# 01_STM32F103RCT6_RNF24L01.net
KiCad netlist of a schematic drawn in Altium Designer
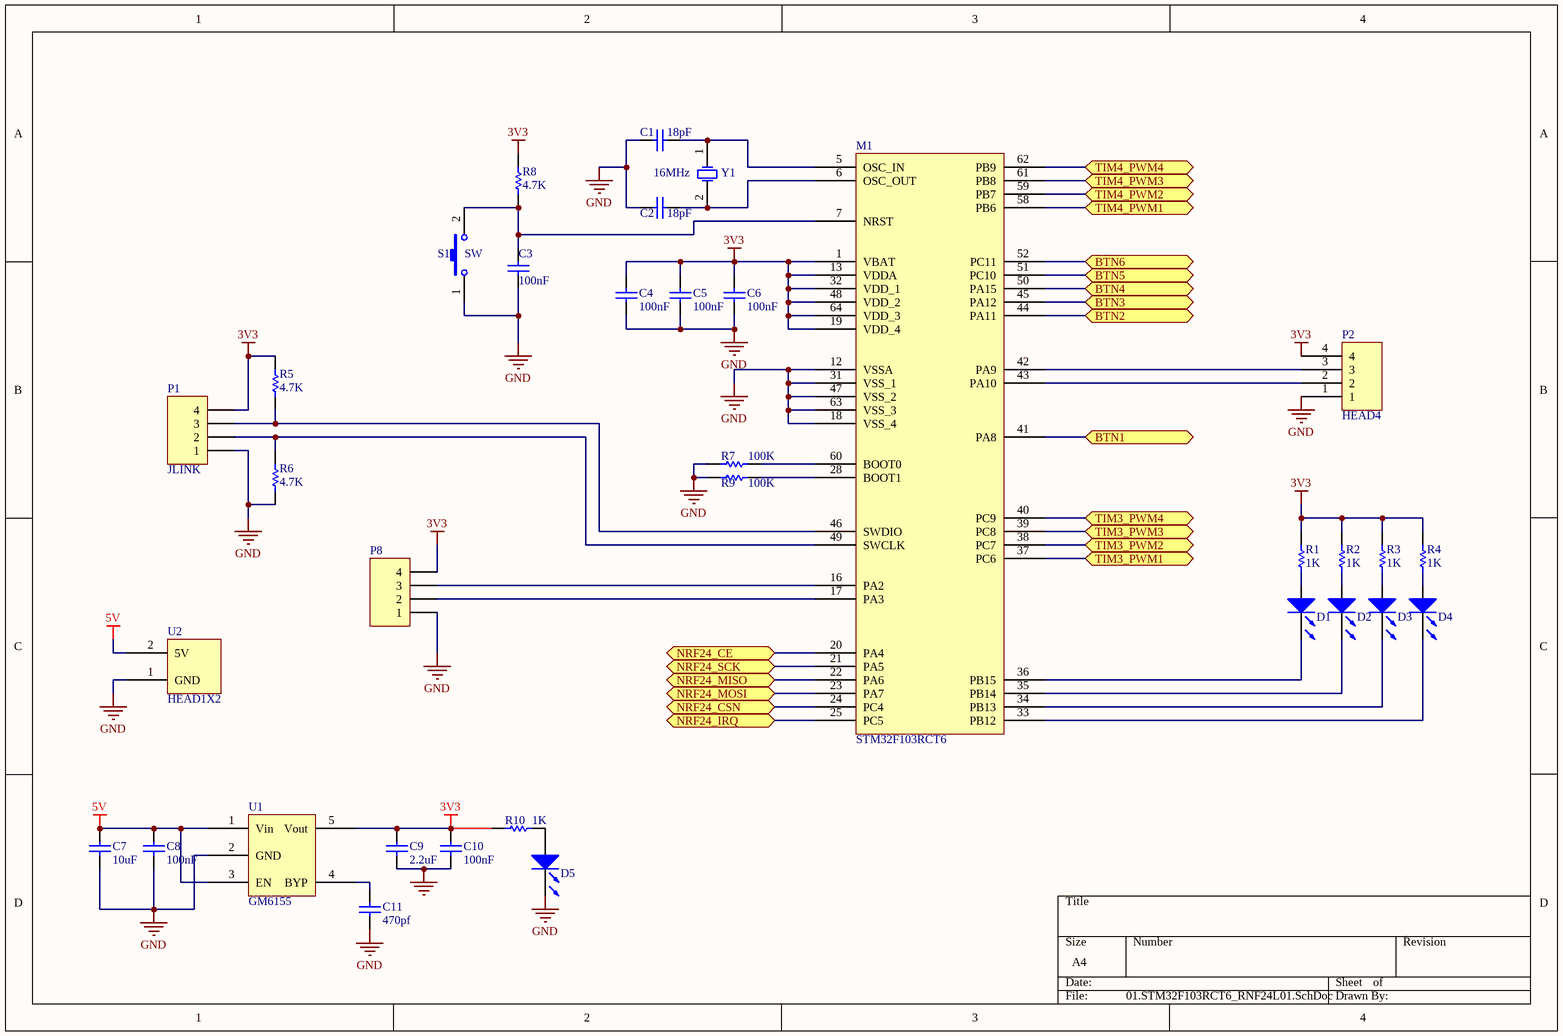
[diagram p0: 01.STM32F103RCT6_RNF24L01.SchDoc]

(export (version "E")
  (design (tool "Eeschema 10.0.6"))
  (components
    (comp (ref "C1")
      (value "18pF")
      (footprint "C1206")
      (description "Capacitor (Semiconductor SIM Model)")
      (fields (field (name "Comment") "Cap Semi") (field (name "PUBLISHER") "Altium Limited"))
      (libsource (lib "Miscellaneous Devices") (part "Cap Semi"))
    )
    (comp (ref "C2")
      (value "18pF")
      (footprint "C1206")
      (description "Capacitor (Semiconductor SIM Model)")
      (fields (field (name "Comment") "Cap Semi") (field (name "PUBLISHER") "Altium Limited"))
      (libsource (lib "Miscellaneous Devices") (part "Cap Semi"))
    )
    (comp (ref "C3")
      (value "100nF")
      (footprint "0805C")
      (description "Capacitor")
      (fields (field (name "PUBLISHER") "Altium Limited"))
      (libsource (lib "YG_SCH_LIB") (part "Cap"))
    )
    (comp (ref "C4")
      (value "100nF")
      (footprint "0805C")
      (description "Capacitor")
      (fields (field (name "PUBLISHER") "Altium Limited"))
      (libsource (lib "YG_SCH_LIB") (part "Cap"))
    )
    (comp (ref "C5")
      (value "100nF")
      (footprint "0805C")
      (description "Capacitor")
      (fields (field (name "PUBLISHER") "Altium Limited"))
      (libsource (lib "YG_SCH_LIB") (part "Cap"))
    )
    (comp (ref "C6")
      (value "100nF")
      (footprint "0805C")
      (description "Capacitor")
      (fields (field (name "PUBLISHER") "Altium Limited"))
      (libsource (lib "YG_SCH_LIB") (part "Cap"))
    )
    (comp (ref "C7")
      (value "10uF")
      (footprint "0805C")
      (description "Capacitor")
      (fields (field (name "PUBLISHER") "Altium Limited"))
      (libsource (lib "YG_SCH_LIB") (part "Cap"))
    )
    (comp (ref "C8")
      (value "100nF")
      (footprint "0805C")
      (description "Capacitor")
      (fields (field (name "PUBLISHER") "Altium Limited"))
      (libsource (lib "YG_SCH_LIB") (part "Cap"))
    )
    (comp (ref "C9")
      (value "2.2uF")
      (footprint "0805C")
      (description "Capacitor")
      (fields (field (name "PUBLISHER") "Altium Limited"))
      (libsource (lib "YG_SCH_LIB") (part "Cap"))
    )
    (comp (ref "C10")
      (value "100nF")
      (footprint "0805C")
      (description "Capacitor")
      (fields (field (name "PUBLISHER") "Altium Limited"))
      (libsource (lib "YG_SCH_LIB") (part "Cap"))
    )
    (comp (ref "C11")
      (value "470pf")
      (footprint "0805C")
      (description "Capacitor")
      (fields (field (name "PUBLISHER") "Altium Limited"))
      (libsource (lib "YG_SCH_LIB") (part "Cap"))
    )
    (comp (ref "D1")
      (value "LED")
      (footprint "0805_LED")
      (description "Typical RED GaAs LED")
      (fields (field (name "PUBLISHER") "Altium Limited"))
      (libsource (lib "YG_SCH_LIB") (part "LED"))
    )
    (comp (ref "D2")
      (value "LED")
      (footprint "0805_LED")
      (description "Typical RED GaAs LED")
      (fields (field (name "PUBLISHER") "Altium Limited"))
      (libsource (lib "YG_SCH_LIB") (part "LED"))
    )
    (comp (ref "D3")
      (value "LED")
      (footprint "0805_LED")
      (description "Typical RED GaAs LED")
      (fields (field (name "PUBLISHER") "Altium Limited"))
      (libsource (lib "YG_SCH_LIB") (part "LED"))
    )
    (comp (ref "D4")
      (value "LED")
      (footprint "0805_LED")
      (description "Typical RED GaAs LED")
      (fields (field (name "PUBLISHER") "Altium Limited"))
      (libsource (lib "YG_SCH_LIB") (part "LED"))
    )
    (comp (ref "D5")
      (value "LED")
      (footprint "0805_LED")
      (description "Typical RED GaAs LED")
      (fields (field (name "PUBLISHER") "Altium Limited"))
      (libsource (lib "YG_SCH_LIB") (part "LED"))
    )
    (comp (ref "M1")
      (value "STM32F103RCT6")
      (footprint "LQFP64")
      (libsource (lib "020.STM32F103RCT6_RNF24L01") (part "STM32F103RCT6"))
    )
    (comp (ref "P1")
      (value "JLINK")
      (footprint "HDR1X4")
      (description "Header, 4-Pin")
      (fields (field (name "PUBLISHER") "Altium Limited"))
      (libsource (lib "YG_SCH_LIB") (part "Header 4"))
    )
    (comp (ref "P2")
      (value "HEAD4")
      (footprint "HDR1X4")
      (libsource (lib "020.STM32F103RCT6_RNF24L01") (part "HEAD4"))
    )
    (comp (ref "P8")
      (value "USART2")
      (footprint "HDR1X4")
      (description "Header, 4-Pin")
      (fields (field (name "PUBLISHER") "Altium Limited"))
      (libsource (lib "YG_SCH_LIB") (part "Header 4"))
    )
    (comp (ref "R1")
      (value "1K")
      (footprint "0805")
      (description "Semiconductor Resistor")
      (fields (field (name "PUBLISHER") "Altium Limited"))
      (libsource (lib "Miscellaneous Devices") (part "Res Semi"))
    )
    (comp (ref "R2")
      (value "1K")
      (footprint "0805")
      (description "Semiconductor Resistor")
      (fields (field (name "PUBLISHER") "Altium Limited"))
      (libsource (lib "Miscellaneous Devices") (part "Res Semi"))
    )
    (comp (ref "R3")
      (value "1K")
      (footprint "0805")
      (description "Semiconductor Resistor")
      (fields (field (name "PUBLISHER") "Altium Limited"))
      (libsource (lib "Miscellaneous Devices") (part "Res Semi"))
    )
    (comp (ref "R4")
      (value "1K")
      (footprint "0805")
      (description "Semiconductor Resistor")
      (fields (field (name "PUBLISHER") "Altium Limited"))
      (libsource (lib "Miscellaneous Devices") (part "Res Semi"))
    )
    (comp (ref "R5")
      (value "4.7K")
      (footprint "0805")
      (description "Semiconductor Resistor")
      (fields (field (name "PUBLISHER") "Altium Limited"))
      (libsource (lib "Miscellaneous Devices") (part "Res Semi"))
    )
    (comp (ref "R6")
      (value "4.7K")
      (footprint "0805")
      (description "Semiconductor Resistor")
      (fields (field (name "PUBLISHER") "Altium Limited"))
      (libsource (lib "Miscellaneous Devices") (part "Res Semi"))
    )
    (comp (ref "R7")
      (value "100K")
      (footprint "0805")
      (description "Semiconductor Resistor")
      (fields (field (name "PUBLISHER") "Altium Limited"))
      (libsource (lib "Miscellaneous Devices") (part "Res Semi"))
    )
    (comp (ref "R8")
      (value "4.7K")
      (footprint "0805")
      (description "Semiconductor Resistor")
      (fields (field (name "PUBLISHER") "Altium Limited"))
      (libsource (lib "Miscellaneous Devices") (part "Res Semi"))
    )
    (comp (ref "R9")
      (value "100K")
      (footprint "0805")
      (description "Semiconductor Resistor")
      (fields (field (name "PUBLISHER") "Altium Limited"))
      (libsource (lib "Miscellaneous Devices") (part "Res Semi"))
    )
    (comp (ref "R10")
      (value "1K")
      (footprint "0805")
      (description "Semiconductor Resistor")
      (fields (field (name "PUBLISHER") "Altium Limited"))
      (libsource (lib "Miscellaneous Devices") (part "Res Semi"))
    )
    (comp (ref "S1")
      (value "SW")
      (footprint "SW4-6X6")
      (description "Switch")
      (fields (field (name "PUBLISHER") "Altium Limited"))
      (libsource (lib "YG_SCH_LIB") (part "SW"))
    )
    (comp (ref "U1")
      (value "GM6155")
      (footprint "SOT-23-5")
      (libsource (lib "RaspberryPi3B_ExtBoard") (part "GM6155"))
    )
    (comp (ref "U2")
      (value "HEAD1X2")
      (footprint "HDR1X2")
      (libsource (lib "020.STM32F103RCT6_RNF24L01") (part "HEAD1X2"))
    )
    (comp (ref "Y1")
      (value "16MHz")
      (footprint "XTAL_SMD")
      (description "Crystal Oscillator")
      (fields (field (name "PUBLISHER") "Altium Limited"))
      (libsource (lib "YG_SCH_LIB") (part "XTAL"))
    )
  )
  (nets
    (net (code "1") (name "/BTN1") (class "Default")
      (node (ref "M1") (pin "41") (pinfunction "PA8_41") (pintype "passive"))
    )
    (net (code "2") (name "/BTN2") (class "Default")
      (node (ref "M1") (pin "44") (pinfunction "PA11_44") (pintype "passive"))
    )
    (net (code "3") (name "/BTN3") (class "Default")
      (node (ref "M1") (pin "45") (pinfunction "PA12_45") (pintype "passive"))
    )
    (net (code "4") (name "/BTN4") (class "Default")
      (node (ref "M1") (pin "50") (pinfunction "PA15_50") (pintype "passive"))
    )
    (net (code "5") (name "/BTN5") (class "Default")
      (node (ref "M1") (pin "51") (pinfunction "PC10_51") (pintype "passive"))
    )
    (net (code "6") (name "/BTN6") (class "Default")
      (node (ref "M1") (pin "52") (pinfunction "PC11_52") (pintype "passive"))
    )
    (net (code "7") (name "/NRF24_CE") (class "Default")
      (node (ref "M1") (pin "20") (pinfunction "PA4_20") (pintype "passive"))
    )
    (net (code "8") (name "/NRF24_CSN") (class "Default")
      (node (ref "M1") (pin "24") (pinfunction "PC4_24") (pintype "passive"))
    )
    (net (code "9") (name "/NRF24_IRQ") (class "Default")
      (node (ref "M1") (pin "25") (pinfunction "PC5_25") (pintype "passive"))
    )
    (net (code "10") (name "/NRF24_MISO") (class "Default")
      (node (ref "M1") (pin "22") (pinfunction "PA6_22") (pintype "passive"))
    )
    (net (code "11") (name "/NRF24_MOSI") (class "Default")
      (node (ref "M1") (pin "23") (pinfunction "PA7_23") (pintype "passive"))
    )
    (net (code "12") (name "/NRF24_SCK") (class "Default")
      (node (ref "M1") (pin "21") (pinfunction "PA5_21") (pintype "passive"))
    )
    (net (code "13") (name "/TIM3_PWM1") (class "Default")
      (node (ref "M1") (pin "37") (pinfunction "PC6_37") (pintype "passive"))
    )
    (net (code "14") (name "/TIM3_PWM2") (class "Default")
      (node (ref "M1") (pin "38") (pinfunction "PC7_38") (pintype "passive"))
    )
    (net (code "15") (name "/TIM3_PWM3") (class "Default")
      (node (ref "M1") (pin "39") (pinfunction "PC8_39") (pintype "passive"))
    )
    (net (code "16") (name "/TIM3_PWM4") (class "Default")
      (node (ref "M1") (pin "40") (pinfunction "PC9_40") (pintype "passive"))
    )
    (net (code "17") (name "/TIM4_PWM1") (class "Default")
      (node (ref "M1") (pin "58") (pinfunction "PB6_58") (pintype "passive"))
    )
    (net (code "18") (name "/TIM4_PWM2") (class "Default")
      (node (ref "M1") (pin "59") (pinfunction "PB7_59") (pintype "passive"))
    )
    (net (code "19") (name "/TIM4_PWM3") (class "Default")
      (node (ref "M1") (pin "61") (pinfunction "PB8_61") (pintype "passive"))
    )
    (net (code "20") (name "/TIM4_PWM4") (class "Default")
      (node (ref "M1") (pin "62") (pinfunction "PB9_62") (pintype "passive"))
    )
    (net (code "21") (name "3V3") (class "Default")
      (node (ref "C10") (pin "1") (pinfunction "1_1") (pintype "passive"))
      (node (ref "C4") (pin "2") (pinfunction "2_2") (pintype "passive"))
      (node (ref "C5") (pin "2") (pinfunction "2_2") (pintype "passive"))
      (node (ref "C6") (pin "2") (pinfunction "2_2") (pintype "passive"))
      (node (ref "C9") (pin "1") (pinfunction "1_1") (pintype "passive"))
      (node (ref "M1") (pin "1") (pinfunction "VBAT_1") (pintype "passive"))
      (node (ref "M1") (pin "13") (pinfunction "VDDA_13") (pintype "passive"))
      (node (ref "M1") (pin "19") (pinfunction "VDD_4_19") (pintype "passive"))
      (node (ref "M1") (pin "32") (pinfunction "VDD_1_32") (pintype "passive"))
      (node (ref "M1") (pin "48") (pinfunction "VDD_2_48") (pintype "passive"))
      (node (ref "M1") (pin "64") (pinfunction "VDD_3_64") (pintype "passive"))
      (node (ref "P1") (pin "4") (pinfunction "4_4") (pintype "passive"))
      (node (ref "P2") (pin "4") (pinfunction "4_4") (pintype "passive"))
      (node (ref "P8") (pin "4") (pinfunction "4_4") (pintype "passive"))
      (node (ref "R1") (pin "1") (pinfunction "1_1") (pintype "passive"))
      (node (ref "R10") (pin "2") (pinfunction "2_2") (pintype "passive"))
      (node (ref "R2") (pin "1") (pinfunction "1_1") (pintype "passive"))
      (node (ref "R3") (pin "1") (pinfunction "1_1") (pintype "passive"))
      (node (ref "R4") (pin "1") (pinfunction "1_1") (pintype "passive"))
      (node (ref "R5") (pin "2") (pinfunction "2_2") (pintype "passive"))
      (node (ref "R8") (pin "1") (pinfunction "1_1") (pintype "passive"))
      (node (ref "U1") (pin "5") (pinfunction "Vout_5") (pintype "passive"))
    )
    (net (code "22") (name "5V") (class "Default")
      (node (ref "C7") (pin "1") (pinfunction "1_1") (pintype "passive"))
      (node (ref "C8") (pin "1") (pinfunction "1_1") (pintype "passive"))
      (node (ref "U1") (pin "1") (pinfunction "Vin_1") (pintype "passive"))
      (node (ref "U1") (pin "3") (pinfunction "EN_3") (pintype "passive"))
      (node (ref "U2") (pin "2") (pinfunction "5V_2") (pintype "passive"))
    )
    (net (code "23") (name "GND") (class "Default")
      (node (ref "C1") (pin "1") (pinfunction "1_1") (pintype "passive"))
      (node (ref "C10") (pin "2") (pinfunction "2_2") (pintype "passive"))
      (node (ref "C11") (pin "1") (pinfunction "1_1") (pintype "passive"))
      (node (ref "C2") (pin "1") (pinfunction "1_1") (pintype "passive"))
      (node (ref "C3") (pin "1") (pinfunction "1_1") (pintype "passive"))
      (node (ref "C4") (pin "1") (pinfunction "1_1") (pintype "passive"))
      (node (ref "C5") (pin "1") (pinfunction "1_1") (pintype "passive"))
      (node (ref "C6") (pin "1") (pinfunction "1_1") (pintype "passive"))
      (node (ref "C7") (pin "2") (pinfunction "2_2") (pintype "passive"))
      (node (ref "C8") (pin "2") (pinfunction "2_2") (pintype "passive"))
      (node (ref "C9") (pin "2") (pinfunction "2_2") (pintype "passive"))
      (node (ref "D5") (pin "2") (pinfunction "K_2") (pintype "passive"))
      (node (ref "M1") (pin "12") (pinfunction "VSSA_12") (pintype "passive"))
      (node (ref "M1") (pin "18") (pinfunction "VSS_4_18") (pintype "passive"))
      (node (ref "M1") (pin "31") (pinfunction "VSS_1_31") (pintype "passive"))
      (node (ref "M1") (pin "47") (pinfunction "VSS_2_47") (pintype "passive"))
      (node (ref "M1") (pin "63") (pinfunction "VSS_3_63") (pintype "passive"))
      (node (ref "P1") (pin "1") (pinfunction "1_1") (pintype "passive"))
      (node (ref "P2") (pin "1") (pinfunction "1_1") (pintype "passive"))
      (node (ref "P8") (pin "1") (pinfunction "1_1") (pintype "passive"))
      (node (ref "R6") (pin "1") (pinfunction "1_1") (pintype "passive"))
      (node (ref "R7") (pin "1") (pinfunction "1_1") (pintype "passive"))
      (node (ref "R9") (pin "1") (pinfunction "1_1") (pintype "passive"))
      (node (ref "S1") (pin "1") (pinfunction "1_1") (pintype "passive"))
      (node (ref "U1") (pin "2") (pinfunction "GND_2") (pintype "passive"))
      (node (ref "U2") (pin "1") (pinfunction "GND_1") (pintype "passive"))
    )
    (net (code "24") (name "Net-(D1-A)") (class "Default")
      (node (ref "D1") (pin "1") (pinfunction "A_1") (pintype "passive"))
      (node (ref "R1") (pin "2") (pinfunction "2_2") (pintype "passive"))
    )
    (net (code "25") (name "Net-(D1-K)") (class "Default")
      (node (ref "D1") (pin "2") (pinfunction "K_2") (pintype "passive"))
      (node (ref "M1") (pin "36") (pinfunction "PB15_36") (pintype "passive"))
    )
    (net (code "26") (name "Net-(D2-A)") (class "Default")
      (node (ref "D2") (pin "1") (pinfunction "A_1") (pintype "passive"))
      (node (ref "R2") (pin "2") (pinfunction "2_2") (pintype "passive"))
    )
    (net (code "27") (name "Net-(D2-K)") (class "Default")
      (node (ref "D2") (pin "2") (pinfunction "K_2") (pintype "passive"))
      (node (ref "M1") (pin "35") (pinfunction "PB14_35") (pintype "passive"))
    )
    (net (code "28") (name "Net-(D3-A)") (class "Default")
      (node (ref "D3") (pin "1") (pinfunction "A_1") (pintype "passive"))
      (node (ref "R3") (pin "2") (pinfunction "2_2") (pintype "passive"))
    )
    (net (code "29") (name "Net-(D3-K)") (class "Default")
      (node (ref "D3") (pin "2") (pinfunction "K_2") (pintype "passive"))
      (node (ref "M1") (pin "34") (pinfunction "PB13_34") (pintype "passive"))
    )
    (net (code "30") (name "Net-(D4-A)") (class "Default")
      (node (ref "D4") (pin "1") (pinfunction "A_1") (pintype "passive"))
      (node (ref "R4") (pin "2") (pinfunction "2_2") (pintype "passive"))
    )
    (net (code "31") (name "Net-(D4-K)") (class "Default")
      (node (ref "D4") (pin "2") (pinfunction "K_2") (pintype "passive"))
      (node (ref "M1") (pin "33") (pinfunction "PB12_33") (pintype "passive"))
    )
    (net (code "32") (name "Net-(D5-A)") (class "Default")
      (node (ref "D5") (pin "1") (pinfunction "A_1") (pintype "passive"))
      (node (ref "R10") (pin "1") (pinfunction "1_1") (pintype "passive"))
    )
    (net (code "33") (name "Net-(M1-BOOT0)") (class "Default")
      (node (ref "M1") (pin "60") (pinfunction "BOOT0_60") (pintype "passive"))
      (node (ref "R7") (pin "2") (pinfunction "2_2") (pintype "passive"))
    )
    (net (code "34") (name "Net-(M1-BOOT1)") (class "Default")
      (node (ref "M1") (pin "28") (pinfunction "BOOT1_28") (pintype "passive"))
      (node (ref "R9") (pin "2") (pinfunction "2_2") (pintype "passive"))
    )
    (net (code "35") (name "Net-(M1-NRST)") (class "Default")
      (node (ref "C3") (pin "2") (pinfunction "2_2") (pintype "passive"))
      (node (ref "M1") (pin "7") (pinfunction "NRST_7") (pintype "passive"))
      (node (ref "R8") (pin "2") (pinfunction "2_2") (pintype "passive"))
      (node (ref "S1") (pin "2") (pinfunction "2_2") (pintype "passive"))
    )
    (net (code "36") (name "Net-(M1-OSC_IN)") (class "Default")
      (node (ref "C1") (pin "2") (pinfunction "2_2") (pintype "passive"))
      (node (ref "M1") (pin "5") (pinfunction "OSC_IN_5") (pintype "passive"))
      (node (ref "Y1") (pin "1") (pinfunction "OSC1_1") (pintype "passive"))
    )
    (net (code "37") (name "Net-(M1-OSC_OUT)") (class "Default")
      (node (ref "C2") (pin "2") (pinfunction "2_2") (pintype "passive"))
      (node (ref "M1") (pin "6") (pinfunction "OSC_OUT_6") (pintype "passive"))
      (node (ref "Y1") (pin "2") (pinfunction "OSC2_2") (pintype "passive"))
    )
    (net (code "38") (name "Net-(M1-PA2)") (class "Default")
      (node (ref "M1") (pin "16") (pinfunction "PA2_16") (pintype "passive"))
      (node (ref "P8") (pin "3") (pinfunction "3_3") (pintype "passive"))
    )
    (net (code "39") (name "Net-(M1-PA3)") (class "Default")
      (node (ref "M1") (pin "17") (pinfunction "PA3_17") (pintype "passive"))
      (node (ref "P8") (pin "2") (pinfunction "2_2") (pintype "passive"))
    )
    (net (code "40") (name "Net-(M1-PA9)") (class "Default")
      (node (ref "M1") (pin "42") (pinfunction "PA9_42") (pintype "passive"))
      (node (ref "P2") (pin "3") (pinfunction "3_3") (pintype "passive"))
    )
    (net (code "41") (name "Net-(M1-PA10)") (class "Default")
      (node (ref "M1") (pin "43") (pinfunction "PA10_43") (pintype "passive"))
      (node (ref "P2") (pin "2") (pinfunction "2_2") (pintype "passive"))
    )
    (net (code "42") (name "Net-(M1-SWCLK)") (class "Default")
      (node (ref "M1") (pin "49") (pinfunction "SWCLK_49") (pintype "passive"))
      (node (ref "P1") (pin "2") (pinfunction "2_2") (pintype "passive"))
      (node (ref "R6") (pin "2") (pinfunction "2_2") (pintype "passive"))
    )
    (net (code "43") (name "Net-(M1-SWDIO)") (class "Default")
      (node (ref "M1") (pin "46") (pinfunction "SWDIO_46") (pintype "passive"))
      (node (ref "P1") (pin "3") (pinfunction "3_3") (pintype "passive"))
      (node (ref "R5") (pin "1") (pinfunction "1_1") (pintype "passive"))
    )
    (net (code "44") (name "Net-(U1-BYP)") (class "Default")
      (node (ref "C11") (pin "2") (pinfunction "2_2") (pintype "passive"))
      (node (ref "U1") (pin "4") (pinfunction "BYP_4") (pintype "passive"))
    )
  )
)
